# WS2812_MATRIX_4.net
KiCad netlist of a schematic drawn in Altium Designer
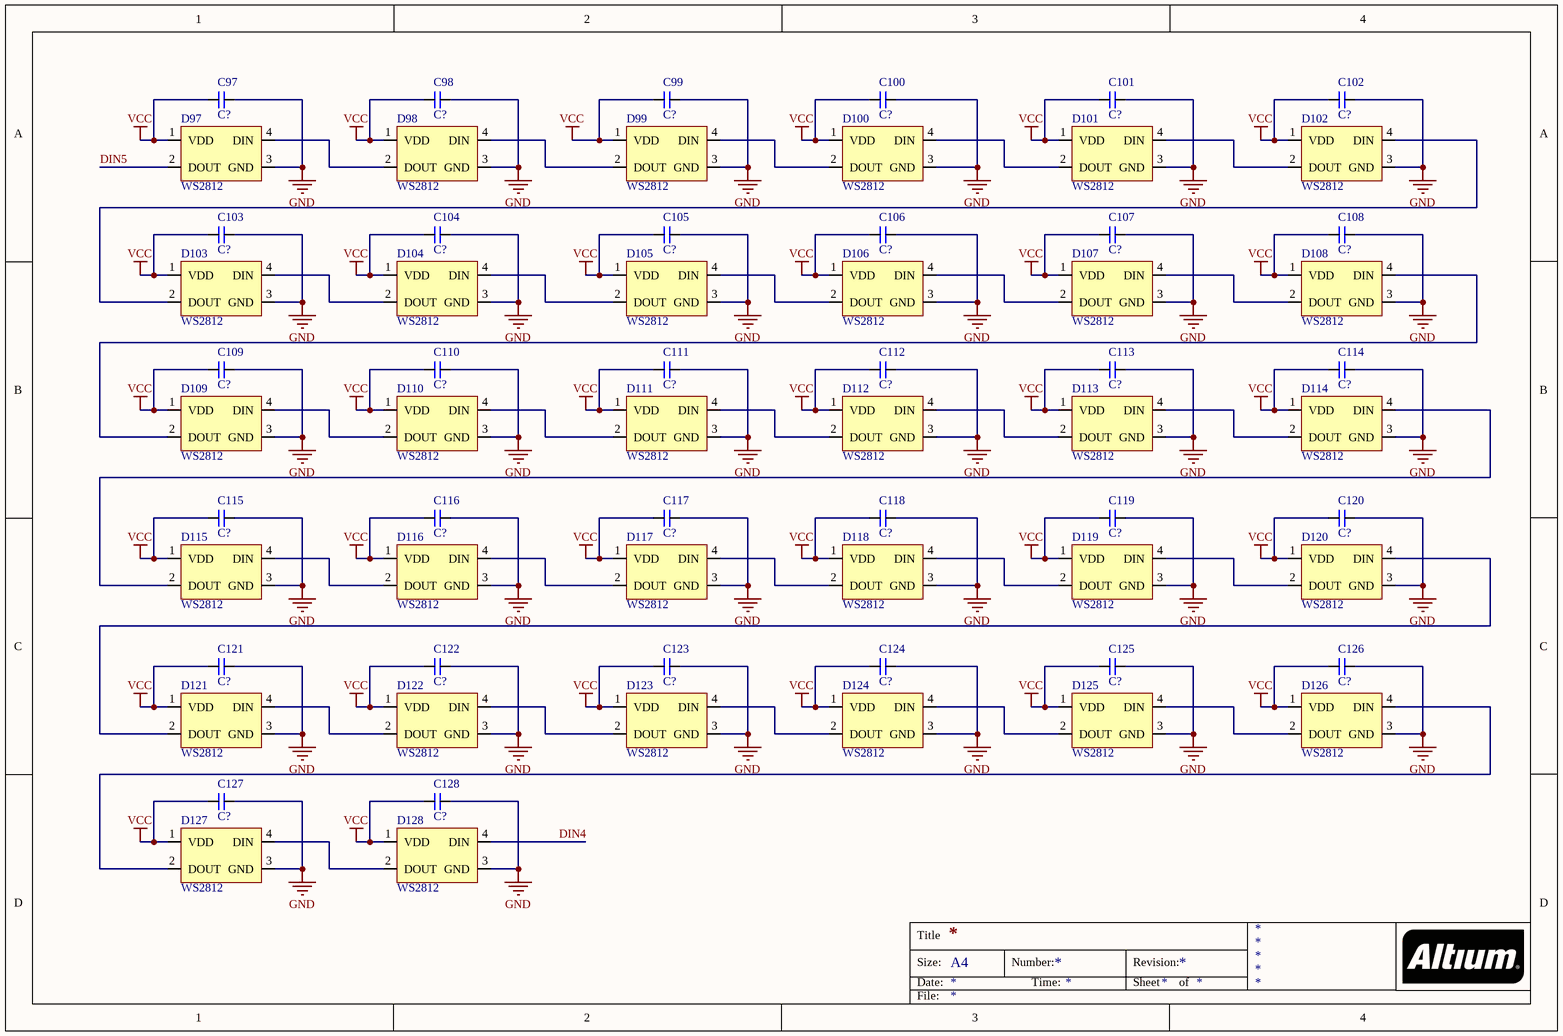
[diagram p0: WS2812_MATRIX_4.SchDoc]

(export (version "E")
  (design (tool "Eeschema 10.0.6"))
  (components
    (comp (ref "C97")
      (value "C?")
      (footprint "C0603")
      (description "Cap")
      (libsource (lib "SCH_Bacsic") (part "CAP"))
    )
    (comp (ref "C98")
      (value "C?")
      (footprint "C0603")
      (description "Cap")
      (libsource (lib "SCH_Bacsic") (part "CAP"))
    )
    (comp (ref "C99")
      (value "C?")
      (footprint "C0603")
      (description "Cap")
      (libsource (lib "SCH_Bacsic") (part "CAP"))
    )
    (comp (ref "C100")
      (value "C?")
      (footprint "C0603")
      (description "Cap")
      (libsource (lib "SCH_Bacsic") (part "CAP"))
    )
    (comp (ref "C101")
      (value "C?")
      (footprint "C0603")
      (description "Cap")
      (libsource (lib "SCH_Bacsic") (part "CAP"))
    )
    (comp (ref "C102")
      (value "C?")
      (footprint "C0603")
      (description "Cap")
      (libsource (lib "SCH_Bacsic") (part "CAP"))
    )
    (comp (ref "C103")
      (value "C?")
      (footprint "C0603")
      (description "Cap")
      (libsource (lib "SCH_Bacsic") (part "CAP"))
    )
    (comp (ref "C104")
      (value "C?")
      (footprint "C0603")
      (description "Cap")
      (libsource (lib "SCH_Bacsic") (part "CAP"))
    )
    (comp (ref "C105")
      (value "C?")
      (footprint "C0603")
      (description "Cap")
      (libsource (lib "SCH_Bacsic") (part "CAP"))
    )
    (comp (ref "C106")
      (value "C?")
      (footprint "C0603")
      (description "Cap")
      (libsource (lib "SCH_Bacsic") (part "CAP"))
    )
    (comp (ref "C107")
      (value "C?")
      (footprint "C0603")
      (description "Cap")
      (libsource (lib "SCH_Bacsic") (part "CAP"))
    )
    (comp (ref "C108")
      (value "C?")
      (footprint "C0603")
      (description "Cap")
      (libsource (lib "SCH_Bacsic") (part "CAP"))
    )
    (comp (ref "C109")
      (value "C?")
      (footprint "C0603")
      (description "Cap")
      (libsource (lib "SCH_Bacsic") (part "CAP"))
    )
    (comp (ref "C110")
      (value "C?")
      (footprint "C0603")
      (description "Cap")
      (libsource (lib "SCH_Bacsic") (part "CAP"))
    )
    (comp (ref "C111")
      (value "C?")
      (footprint "C0603")
      (description "Cap")
      (libsource (lib "SCH_Bacsic") (part "CAP"))
    )
    (comp (ref "C112")
      (value "C?")
      (footprint "C0603")
      (description "Cap")
      (libsource (lib "SCH_Bacsic") (part "CAP"))
    )
    (comp (ref "C113")
      (value "C?")
      (footprint "C0603")
      (description "Cap")
      (libsource (lib "SCH_Bacsic") (part "CAP"))
    )
    (comp (ref "C114")
      (value "C?")
      (footprint "C0603")
      (description "Cap")
      (libsource (lib "SCH_Bacsic") (part "CAP"))
    )
    (comp (ref "C115")
      (value "C?")
      (footprint "C0603")
      (description "Cap")
      (libsource (lib "SCH_Bacsic") (part "CAP"))
    )
    (comp (ref "C116")
      (value "C?")
      (footprint "C0603")
      (description "Cap")
      (libsource (lib "SCH_Bacsic") (part "CAP"))
    )
    (comp (ref "C117")
      (value "C?")
      (footprint "C0603")
      (description "Cap")
      (libsource (lib "SCH_Bacsic") (part "CAP"))
    )
    (comp (ref "C118")
      (value "C?")
      (footprint "C0603")
      (description "Cap")
      (libsource (lib "SCH_Bacsic") (part "CAP"))
    )
    (comp (ref "C119")
      (value "C?")
      (footprint "C0603")
      (description "Cap")
      (libsource (lib "SCH_Bacsic") (part "CAP"))
    )
    (comp (ref "C120")
      (value "C?")
      (footprint "C0603")
      (description "Cap")
      (libsource (lib "SCH_Bacsic") (part "CAP"))
    )
    (comp (ref "C121")
      (value "C?")
      (footprint "C0603")
      (description "Cap")
      (libsource (lib "SCH_Bacsic") (part "CAP"))
    )
    (comp (ref "C122")
      (value "C?")
      (footprint "C0603")
      (description "Cap")
      (libsource (lib "SCH_Bacsic") (part "CAP"))
    )
    (comp (ref "C123")
      (value "C?")
      (footprint "C0603")
      (description "Cap")
      (libsource (lib "SCH_Bacsic") (part "CAP"))
    )
    (comp (ref "C124")
      (value "C?")
      (footprint "C0603")
      (description "Cap")
      (libsource (lib "SCH_Bacsic") (part "CAP"))
    )
    (comp (ref "C125")
      (value "C?")
      (footprint "C0603")
      (description "Cap")
      (libsource (lib "SCH_Bacsic") (part "CAP"))
    )
    (comp (ref "C126")
      (value "C?")
      (footprint "C0603")
      (description "Cap")
      (libsource (lib "SCH_Bacsic") (part "CAP"))
    )
    (comp (ref "C127")
      (value "C?")
      (footprint "C0603")
      (description "Cap")
      (libsource (lib "SCH_Bacsic") (part "CAP"))
    )
    (comp (ref "C128")
      (value "C?")
      (footprint "C0603")
      (description "Cap")
      (libsource (lib "SCH_Bacsic") (part "CAP"))
    )
    (comp (ref "D97")
      (value "WS2812")
      (footprint "WS2812_3528")
      (libsource (lib "SCH_Bacsic") (part "WS2812"))
    )
    (comp (ref "D98")
      (value "WS2812")
      (footprint "WS2812_3528")
      (libsource (lib "SCH_Bacsic") (part "WS2812"))
    )
    (comp (ref "D99")
      (value "WS2812")
      (footprint "WS2812_3528")
      (libsource (lib "SCH_Bacsic") (part "WS2812"))
    )
    (comp (ref "D100")
      (value "WS2812")
      (footprint "WS2812_3528")
      (libsource (lib "SCH_Bacsic") (part "WS2812"))
    )
    (comp (ref "D101")
      (value "WS2812")
      (footprint "WS2812_3528")
      (libsource (lib "SCH_Bacsic") (part "WS2812"))
    )
    (comp (ref "D102")
      (value "WS2812")
      (footprint "WS2812_3528")
      (libsource (lib "SCH_Bacsic") (part "WS2812"))
    )
    (comp (ref "D103")
      (value "WS2812")
      (footprint "WS2812_3528")
      (libsource (lib "SCH_Bacsic") (part "WS2812"))
    )
    (comp (ref "D104")
      (value "WS2812")
      (footprint "WS2812_3528")
      (libsource (lib "SCH_Bacsic") (part "WS2812"))
    )
    (comp (ref "D105")
      (value "WS2812")
      (footprint "WS2812_3528")
      (libsource (lib "SCH_Bacsic") (part "WS2812"))
    )
    (comp (ref "D106")
      (value "WS2812")
      (footprint "WS2812_3528")
      (libsource (lib "SCH_Bacsic") (part "WS2812"))
    )
    (comp (ref "D107")
      (value "WS2812")
      (footprint "WS2812_3528")
      (libsource (lib "SCH_Bacsic") (part "WS2812"))
    )
    (comp (ref "D108")
      (value "WS2812")
      (footprint "WS2812_3528")
      (libsource (lib "SCH_Bacsic") (part "WS2812"))
    )
    (comp (ref "D109")
      (value "WS2812")
      (footprint "WS2812_3528")
      (libsource (lib "SCH_Bacsic") (part "WS2812"))
    )
    (comp (ref "D110")
      (value "WS2812")
      (footprint "WS2812_3528")
      (libsource (lib "SCH_Bacsic") (part "WS2812"))
    )
    (comp (ref "D111")
      (value "WS2812")
      (footprint "WS2812_3528")
      (libsource (lib "SCH_Bacsic") (part "WS2812"))
    )
    (comp (ref "D112")
      (value "WS2812")
      (footprint "WS2812_3528")
      (libsource (lib "SCH_Bacsic") (part "WS2812"))
    )
    (comp (ref "D113")
      (value "WS2812")
      (footprint "WS2812_3528")
      (libsource (lib "SCH_Bacsic") (part "WS2812"))
    )
    (comp (ref "D114")
      (value "WS2812")
      (footprint "WS2812_3528")
      (libsource (lib "SCH_Bacsic") (part "WS2812"))
    )
    (comp (ref "D115")
      (value "WS2812")
      (footprint "WS2812_3528")
      (libsource (lib "SCH_Bacsic") (part "WS2812"))
    )
    (comp (ref "D116")
      (value "WS2812")
      (footprint "WS2812_3528")
      (libsource (lib "SCH_Bacsic") (part "WS2812"))
    )
    (comp (ref "D117")
      (value "WS2812")
      (footprint "WS2812_3528")
      (libsource (lib "SCH_Bacsic") (part "WS2812"))
    )
    (comp (ref "D118")
      (value "WS2812")
      (footprint "WS2812_3528")
      (libsource (lib "SCH_Bacsic") (part "WS2812"))
    )
    (comp (ref "D119")
      (value "WS2812")
      (footprint "WS2812_3528")
      (libsource (lib "SCH_Bacsic") (part "WS2812"))
    )
    (comp (ref "D120")
      (value "WS2812")
      (footprint "WS2812_3528")
      (libsource (lib "SCH_Bacsic") (part "WS2812"))
    )
    (comp (ref "D121")
      (value "WS2812")
      (footprint "WS2812_3528")
      (libsource (lib "SCH_Bacsic") (part "WS2812"))
    )
    (comp (ref "D122")
      (value "WS2812")
      (footprint "WS2812_3528")
      (libsource (lib "SCH_Bacsic") (part "WS2812"))
    )
    (comp (ref "D123")
      (value "WS2812")
      (footprint "WS2812_3528")
      (libsource (lib "SCH_Bacsic") (part "WS2812"))
    )
    (comp (ref "D124")
      (value "WS2812")
      (footprint "WS2812_3528")
      (libsource (lib "SCH_Bacsic") (part "WS2812"))
    )
    (comp (ref "D125")
      (value "WS2812")
      (footprint "WS2812_3528")
      (libsource (lib "SCH_Bacsic") (part "WS2812"))
    )
    (comp (ref "D126")
      (value "WS2812")
      (footprint "WS2812_3528")
      (libsource (lib "SCH_Bacsic") (part "WS2812"))
    )
    (comp (ref "D127")
      (value "WS2812")
      (footprint "WS2812_3528")
      (libsource (lib "SCH_Bacsic") (part "WS2812"))
    )
    (comp (ref "D128")
      (value "WS2812")
      (footprint "WS2812_3528")
      (libsource (lib "SCH_Bacsic") (part "WS2812"))
    )
  )
  (nets
    (net (code "1") (name "/DIN4") (class "Default")
      (node (ref "D128") (pin "4") (pinfunction "DIN_4") (pintype "passive"))
    )
    (net (code "2") (name "/DIN5") (class "Default")
      (node (ref "D97") (pin "2") (pinfunction "DOUT_2") (pintype "passive"))
    )
    (net (code "3") (name "GND") (class "Default")
      (node (ref "C100") (pin "2") (pintype "passive"))
      (node (ref "C101") (pin "2") (pintype "passive"))
      (node (ref "C102") (pin "2") (pintype "passive"))
      (node (ref "C103") (pin "2") (pintype "passive"))
      (node (ref "C104") (pin "2") (pintype "passive"))
      (node (ref "C105") (pin "2") (pintype "passive"))
      (node (ref "C106") (pin "2") (pintype "passive"))
      (node (ref "C107") (pin "2") (pintype "passive"))
      (node (ref "C108") (pin "2") (pintype "passive"))
      (node (ref "C109") (pin "2") (pintype "passive"))
      (node (ref "C110") (pin "2") (pintype "passive"))
      (node (ref "C111") (pin "2") (pintype "passive"))
      (node (ref "C112") (pin "2") (pintype "passive"))
      (node (ref "C113") (pin "2") (pintype "passive"))
      (node (ref "C114") (pin "2") (pintype "passive"))
      (node (ref "C115") (pin "2") (pintype "passive"))
      (node (ref "C116") (pin "2") (pintype "passive"))
      (node (ref "C117") (pin "2") (pintype "passive"))
      (node (ref "C118") (pin "2") (pintype "passive"))
      (node (ref "C119") (pin "2") (pintype "passive"))
      (node (ref "C120") (pin "2") (pintype "passive"))
      (node (ref "C121") (pin "2") (pintype "passive"))
      (node (ref "C122") (pin "2") (pintype "passive"))
      (node (ref "C123") (pin "2") (pintype "passive"))
      (node (ref "C124") (pin "2") (pintype "passive"))
      (node (ref "C125") (pin "2") (pintype "passive"))
      (node (ref "C126") (pin "2") (pintype "passive"))
      (node (ref "C127") (pin "2") (pintype "passive"))
      (node (ref "C128") (pin "2") (pintype "passive"))
      (node (ref "C97") (pin "2") (pintype "passive"))
      (node (ref "C98") (pin "2") (pintype "passive"))
      (node (ref "C99") (pin "2") (pintype "passive"))
      (node (ref "D100") (pin "3") (pinfunction "GND_3") (pintype "passive"))
      (node (ref "D101") (pin "3") (pinfunction "GND_3") (pintype "passive"))
      (node (ref "D102") (pin "3") (pinfunction "GND_3") (pintype "passive"))
      (node (ref "D103") (pin "3") (pinfunction "GND_3") (pintype "passive"))
      (node (ref "D104") (pin "3") (pinfunction "GND_3") (pintype "passive"))
      (node (ref "D105") (pin "3") (pinfunction "GND_3") (pintype "passive"))
      (node (ref "D106") (pin "3") (pinfunction "GND_3") (pintype "passive"))
      (node (ref "D107") (pin "3") (pinfunction "GND_3") (pintype "passive"))
      (node (ref "D108") (pin "3") (pinfunction "GND_3") (pintype "passive"))
      (node (ref "D109") (pin "3") (pinfunction "GND_3") (pintype "passive"))
      (node (ref "D110") (pin "3") (pinfunction "GND_3") (pintype "passive"))
      (node (ref "D111") (pin "3") (pinfunction "GND_3") (pintype "passive"))
      (node (ref "D112") (pin "3") (pinfunction "GND_3") (pintype "passive"))
      (node (ref "D113") (pin "3") (pinfunction "GND_3") (pintype "passive"))
      (node (ref "D114") (pin "3") (pinfunction "GND_3") (pintype "passive"))
      (node (ref "D115") (pin "3") (pinfunction "GND_3") (pintype "passive"))
      (node (ref "D116") (pin "3") (pinfunction "GND_3") (pintype "passive"))
      (node (ref "D117") (pin "3") (pinfunction "GND_3") (pintype "passive"))
      (node (ref "D118") (pin "3") (pinfunction "GND_3") (pintype "passive"))
      (node (ref "D119") (pin "3") (pinfunction "GND_3") (pintype "passive"))
      (node (ref "D120") (pin "3") (pinfunction "GND_3") (pintype "passive"))
      (node (ref "D121") (pin "3") (pinfunction "GND_3") (pintype "passive"))
      (node (ref "D122") (pin "3") (pinfunction "GND_3") (pintype "passive"))
      (node (ref "D123") (pin "3") (pinfunction "GND_3") (pintype "passive"))
      (node (ref "D124") (pin "3") (pinfunction "GND_3") (pintype "passive"))
      (node (ref "D125") (pin "3") (pinfunction "GND_3") (pintype "passive"))
      (node (ref "D126") (pin "3") (pinfunction "GND_3") (pintype "passive"))
      (node (ref "D127") (pin "3") (pinfunction "GND_3") (pintype "passive"))
      (node (ref "D128") (pin "3") (pinfunction "GND_3") (pintype "passive"))
      (node (ref "D97") (pin "3") (pinfunction "GND_3") (pintype "passive"))
      (node (ref "D98") (pin "3") (pinfunction "GND_3") (pintype "passive"))
      (node (ref "D99") (pin "3") (pinfunction "GND_3") (pintype "passive"))
    )
    (net (code "4") (name "Net-(D97-DIN)") (class "Default")
      (node (ref "D97") (pin "4") (pinfunction "DIN_4") (pintype "passive"))
      (node (ref "D98") (pin "2") (pinfunction "DOUT_2") (pintype "passive"))
    )
    (net (code "5") (name "Net-(D98-DIN)") (class "Default")
      (node (ref "D98") (pin "4") (pinfunction "DIN_4") (pintype "passive"))
      (node (ref "D99") (pin "2") (pinfunction "DOUT_2") (pintype "passive"))
    )
    (net (code "6") (name "Net-(D100-DIN)") (class "Default")
      (node (ref "D100") (pin "4") (pinfunction "DIN_4") (pintype "passive"))
      (node (ref "D101") (pin "2") (pinfunction "DOUT_2") (pintype "passive"))
    )
    (net (code "7") (name "Net-(D100-DOUT)") (class "Default")
      (node (ref "D100") (pin "2") (pinfunction "DOUT_2") (pintype "passive"))
      (node (ref "D99") (pin "4") (pinfunction "DIN_4") (pintype "passive"))
    )
    (net (code "8") (name "Net-(D101-DIN)") (class "Default")
      (node (ref "D101") (pin "4") (pinfunction "DIN_4") (pintype "passive"))
      (node (ref "D102") (pin "2") (pinfunction "DOUT_2") (pintype "passive"))
    )
    (net (code "9") (name "Net-(D102-DIN)") (class "Default")
      (node (ref "D102") (pin "4") (pinfunction "DIN_4") (pintype "passive"))
      (node (ref "D103") (pin "2") (pinfunction "DOUT_2") (pintype "passive"))
    )
    (net (code "10") (name "Net-(D103-DIN)") (class "Default")
      (node (ref "D103") (pin "4") (pinfunction "DIN_4") (pintype "passive"))
      (node (ref "D104") (pin "2") (pinfunction "DOUT_2") (pintype "passive"))
    )
    (net (code "11") (name "Net-(D104-DIN)") (class "Default")
      (node (ref "D104") (pin "4") (pinfunction "DIN_4") (pintype "passive"))
      (node (ref "D105") (pin "2") (pinfunction "DOUT_2") (pintype "passive"))
    )
    (net (code "12") (name "Net-(D105-DIN)") (class "Default")
      (node (ref "D105") (pin "4") (pinfunction "DIN_4") (pintype "passive"))
      (node (ref "D106") (pin "2") (pinfunction "DOUT_2") (pintype "passive"))
    )
    (net (code "13") (name "Net-(D106-DIN)") (class "Default")
      (node (ref "D106") (pin "4") (pinfunction "DIN_4") (pintype "passive"))
      (node (ref "D107") (pin "2") (pinfunction "DOUT_2") (pintype "passive"))
    )
    (net (code "14") (name "Net-(D107-DIN)") (class "Default")
      (node (ref "D107") (pin "4") (pinfunction "DIN_4") (pintype "passive"))
      (node (ref "D108") (pin "2") (pinfunction "DOUT_2") (pintype "passive"))
    )
    (net (code "15") (name "Net-(D108-DIN)") (class "Default")
      (node (ref "D108") (pin "4") (pinfunction "DIN_4") (pintype "passive"))
      (node (ref "D109") (pin "2") (pinfunction "DOUT_2") (pintype "passive"))
    )
    (net (code "16") (name "Net-(D109-DIN)") (class "Default")
      (node (ref "D109") (pin "4") (pinfunction "DIN_4") (pintype "passive"))
      (node (ref "D110") (pin "2") (pinfunction "DOUT_2") (pintype "passive"))
    )
    (net (code "17") (name "Net-(D110-DIN)") (class "Default")
      (node (ref "D110") (pin "4") (pinfunction "DIN_4") (pintype "passive"))
      (node (ref "D111") (pin "2") (pinfunction "DOUT_2") (pintype "passive"))
    )
    (net (code "18") (name "Net-(D111-DIN)") (class "Default")
      (node (ref "D111") (pin "4") (pinfunction "DIN_4") (pintype "passive"))
      (node (ref "D112") (pin "2") (pinfunction "DOUT_2") (pintype "passive"))
    )
    (net (code "19") (name "Net-(D112-DIN)") (class "Default")
      (node (ref "D112") (pin "4") (pinfunction "DIN_4") (pintype "passive"))
      (node (ref "D113") (pin "2") (pinfunction "DOUT_2") (pintype "passive"))
    )
    (net (code "20") (name "Net-(D113-DIN)") (class "Default")
      (node (ref "D113") (pin "4") (pinfunction "DIN_4") (pintype "passive"))
      (node (ref "D114") (pin "2") (pinfunction "DOUT_2") (pintype "passive"))
    )
    (net (code "21") (name "Net-(D114-DIN)") (class "Default")
      (node (ref "D114") (pin "4") (pinfunction "DIN_4") (pintype "passive"))
      (node (ref "D115") (pin "2") (pinfunction "DOUT_2") (pintype "passive"))
    )
    (net (code "22") (name "Net-(D115-DIN)") (class "Default")
      (node (ref "D115") (pin "4") (pinfunction "DIN_4") (pintype "passive"))
      (node (ref "D116") (pin "2") (pinfunction "DOUT_2") (pintype "passive"))
    )
    (net (code "23") (name "Net-(D116-DIN)") (class "Default")
      (node (ref "D116") (pin "4") (pinfunction "DIN_4") (pintype "passive"))
      (node (ref "D117") (pin "2") (pinfunction "DOUT_2") (pintype "passive"))
    )
    (net (code "24") (name "Net-(D117-DIN)") (class "Default")
      (node (ref "D117") (pin "4") (pinfunction "DIN_4") (pintype "passive"))
      (node (ref "D118") (pin "2") (pinfunction "DOUT_2") (pintype "passive"))
    )
    (net (code "25") (name "Net-(D118-DIN)") (class "Default")
      (node (ref "D118") (pin "4") (pinfunction "DIN_4") (pintype "passive"))
      (node (ref "D119") (pin "2") (pinfunction "DOUT_2") (pintype "passive"))
    )
    (net (code "26") (name "Net-(D119-DIN)") (class "Default")
      (node (ref "D119") (pin "4") (pinfunction "DIN_4") (pintype "passive"))
      (node (ref "D120") (pin "2") (pinfunction "DOUT_2") (pintype "passive"))
    )
    (net (code "27") (name "Net-(D120-DIN)") (class "Default")
      (node (ref "D120") (pin "4") (pinfunction "DIN_4") (pintype "passive"))
      (node (ref "D121") (pin "2") (pinfunction "DOUT_2") (pintype "passive"))
    )
    (net (code "28") (name "Net-(D121-DIN)") (class "Default")
      (node (ref "D121") (pin "4") (pinfunction "DIN_4") (pintype "passive"))
      (node (ref "D122") (pin "2") (pinfunction "DOUT_2") (pintype "passive"))
    )
    (net (code "29") (name "Net-(D122-DIN)") (class "Default")
      (node (ref "D122") (pin "4") (pinfunction "DIN_4") (pintype "passive"))
      (node (ref "D123") (pin "2") (pinfunction "DOUT_2") (pintype "passive"))
    )
    (net (code "30") (name "Net-(D123-DIN)") (class "Default")
      (node (ref "D123") (pin "4") (pinfunction "DIN_4") (pintype "passive"))
      (node (ref "D124") (pin "2") (pinfunction "DOUT_2") (pintype "passive"))
    )
    (net (code "31") (name "Net-(D124-DIN)") (class "Default")
      (node (ref "D124") (pin "4") (pinfunction "DIN_4") (pintype "passive"))
      (node (ref "D125") (pin "2") (pinfunction "DOUT_2") (pintype "passive"))
    )
    (net (code "32") (name "Net-(D125-DIN)") (class "Default")
      (node (ref "D125") (pin "4") (pinfunction "DIN_4") (pintype "passive"))
      (node (ref "D126") (pin "2") (pinfunction "DOUT_2") (pintype "passive"))
    )
    (net (code "33") (name "Net-(D126-DIN)") (class "Default")
      (node (ref "D126") (pin "4") (pinfunction "DIN_4") (pintype "passive"))
      (node (ref "D127") (pin "2") (pinfunction "DOUT_2") (pintype "passive"))
    )
    (net (code "34") (name "Net-(D127-DIN)") (class "Default")
      (node (ref "D127") (pin "4") (pinfunction "DIN_4") (pintype "passive"))
      (node (ref "D128") (pin "2") (pinfunction "DOUT_2") (pintype "passive"))
    )
    (net (code "35") (name "VCC") (class "Default")
      (node (ref "C100") (pin "1") (pintype "passive"))
      (node (ref "C101") (pin "1") (pintype "passive"))
      (node (ref "C102") (pin "1") (pintype "passive"))
      (node (ref "C103") (pin "1") (pintype "passive"))
      (node (ref "C104") (pin "1") (pintype "passive"))
      (node (ref "C105") (pin "1") (pintype "passive"))
      (node (ref "C106") (pin "1") (pintype "passive"))
      (node (ref "C107") (pin "1") (pintype "passive"))
      (node (ref "C108") (pin "1") (pintype "passive"))
      (node (ref "C109") (pin "1") (pintype "passive"))
      (node (ref "C110") (pin "1") (pintype "passive"))
      (node (ref "C111") (pin "1") (pintype "passive"))
      (node (ref "C112") (pin "1") (pintype "passive"))
      (node (ref "C113") (pin "1") (pintype "passive"))
      (node (ref "C114") (pin "1") (pintype "passive"))
      (node (ref "C115") (pin "1") (pintype "passive"))
      (node (ref "C116") (pin "1") (pintype "passive"))
      (node (ref "C117") (pin "1") (pintype "passive"))
      (node (ref "C118") (pin "1") (pintype "passive"))
      (node (ref "C119") (pin "1") (pintype "passive"))
      (node (ref "C120") (pin "1") (pintype "passive"))
      (node (ref "C121") (pin "1") (pintype "passive"))
      (node (ref "C122") (pin "1") (pintype "passive"))
      (node (ref "C123") (pin "1") (pintype "passive"))
      (node (ref "C124") (pin "1") (pintype "passive"))
      (node (ref "C125") (pin "1") (pintype "passive"))
      (node (ref "C126") (pin "1") (pintype "passive"))
      (node (ref "C127") (pin "1") (pintype "passive"))
      (node (ref "C128") (pin "1") (pintype "passive"))
      (node (ref "C97") (pin "1") (pintype "passive"))
      (node (ref "C98") (pin "1") (pintype "passive"))
      (node (ref "C99") (pin "1") (pintype "passive"))
      (node (ref "D100") (pin "1") (pinfunction "VDD_1") (pintype "passive"))
      (node (ref "D101") (pin "1") (pinfunction "VDD_1") (pintype "passive"))
      (node (ref "D102") (pin "1") (pinfunction "VDD_1") (pintype "passive"))
      (node (ref "D103") (pin "1") (pinfunction "VDD_1") (pintype "passive"))
      (node (ref "D104") (pin "1") (pinfunction "VDD_1") (pintype "passive"))
      (node (ref "D105") (pin "1") (pinfunction "VDD_1") (pintype "passive"))
      (node (ref "D106") (pin "1") (pinfunction "VDD_1") (pintype "passive"))
      (node (ref "D107") (pin "1") (pinfunction "VDD_1") (pintype "passive"))
      (node (ref "D108") (pin "1") (pinfunction "VDD_1") (pintype "passive"))
      (node (ref "D109") (pin "1") (pinfunction "VDD_1") (pintype "passive"))
      (node (ref "D110") (pin "1") (pinfunction "VDD_1") (pintype "passive"))
      (node (ref "D111") (pin "1") (pinfunction "VDD_1") (pintype "passive"))
      (node (ref "D112") (pin "1") (pinfunction "VDD_1") (pintype "passive"))
      (node (ref "D113") (pin "1") (pinfunction "VDD_1") (pintype "passive"))
      (node (ref "D114") (pin "1") (pinfunction "VDD_1") (pintype "passive"))
      (node (ref "D115") (pin "1") (pinfunction "VDD_1") (pintype "passive"))
      (node (ref "D116") (pin "1") (pinfunction "VDD_1") (pintype "passive"))
      (node (ref "D117") (pin "1") (pinfunction "VDD_1") (pintype "passive"))
      (node (ref "D118") (pin "1") (pinfunction "VDD_1") (pintype "passive"))
      (node (ref "D119") (pin "1") (pinfunction "VDD_1") (pintype "passive"))
      (node (ref "D120") (pin "1") (pinfunction "VDD_1") (pintype "passive"))
      (node (ref "D121") (pin "1") (pinfunction "VDD_1") (pintype "passive"))
      (node (ref "D122") (pin "1") (pinfunction "VDD_1") (pintype "passive"))
      (node (ref "D123") (pin "1") (pinfunction "VDD_1") (pintype "passive"))
      (node (ref "D124") (pin "1") (pinfunction "VDD_1") (pintype "passive"))
      (node (ref "D125") (pin "1") (pinfunction "VDD_1") (pintype "passive"))
      (node (ref "D126") (pin "1") (pinfunction "VDD_1") (pintype "passive"))
      (node (ref "D127") (pin "1") (pinfunction "VDD_1") (pintype "passive"))
      (node (ref "D128") (pin "1") (pinfunction "VDD_1") (pintype "passive"))
      (node (ref "D97") (pin "1") (pinfunction "VDD_1") (pintype "passive"))
      (node (ref "D98") (pin "1") (pinfunction "VDD_1") (pintype "passive"))
      (node (ref "D99") (pin "1") (pinfunction "VDD_1") (pintype "passive"))
    )
  )
)
